# T-Board-45-85_PCB_-_v0_1.net
KiCad netlist of a schematic drawn in EAGLE
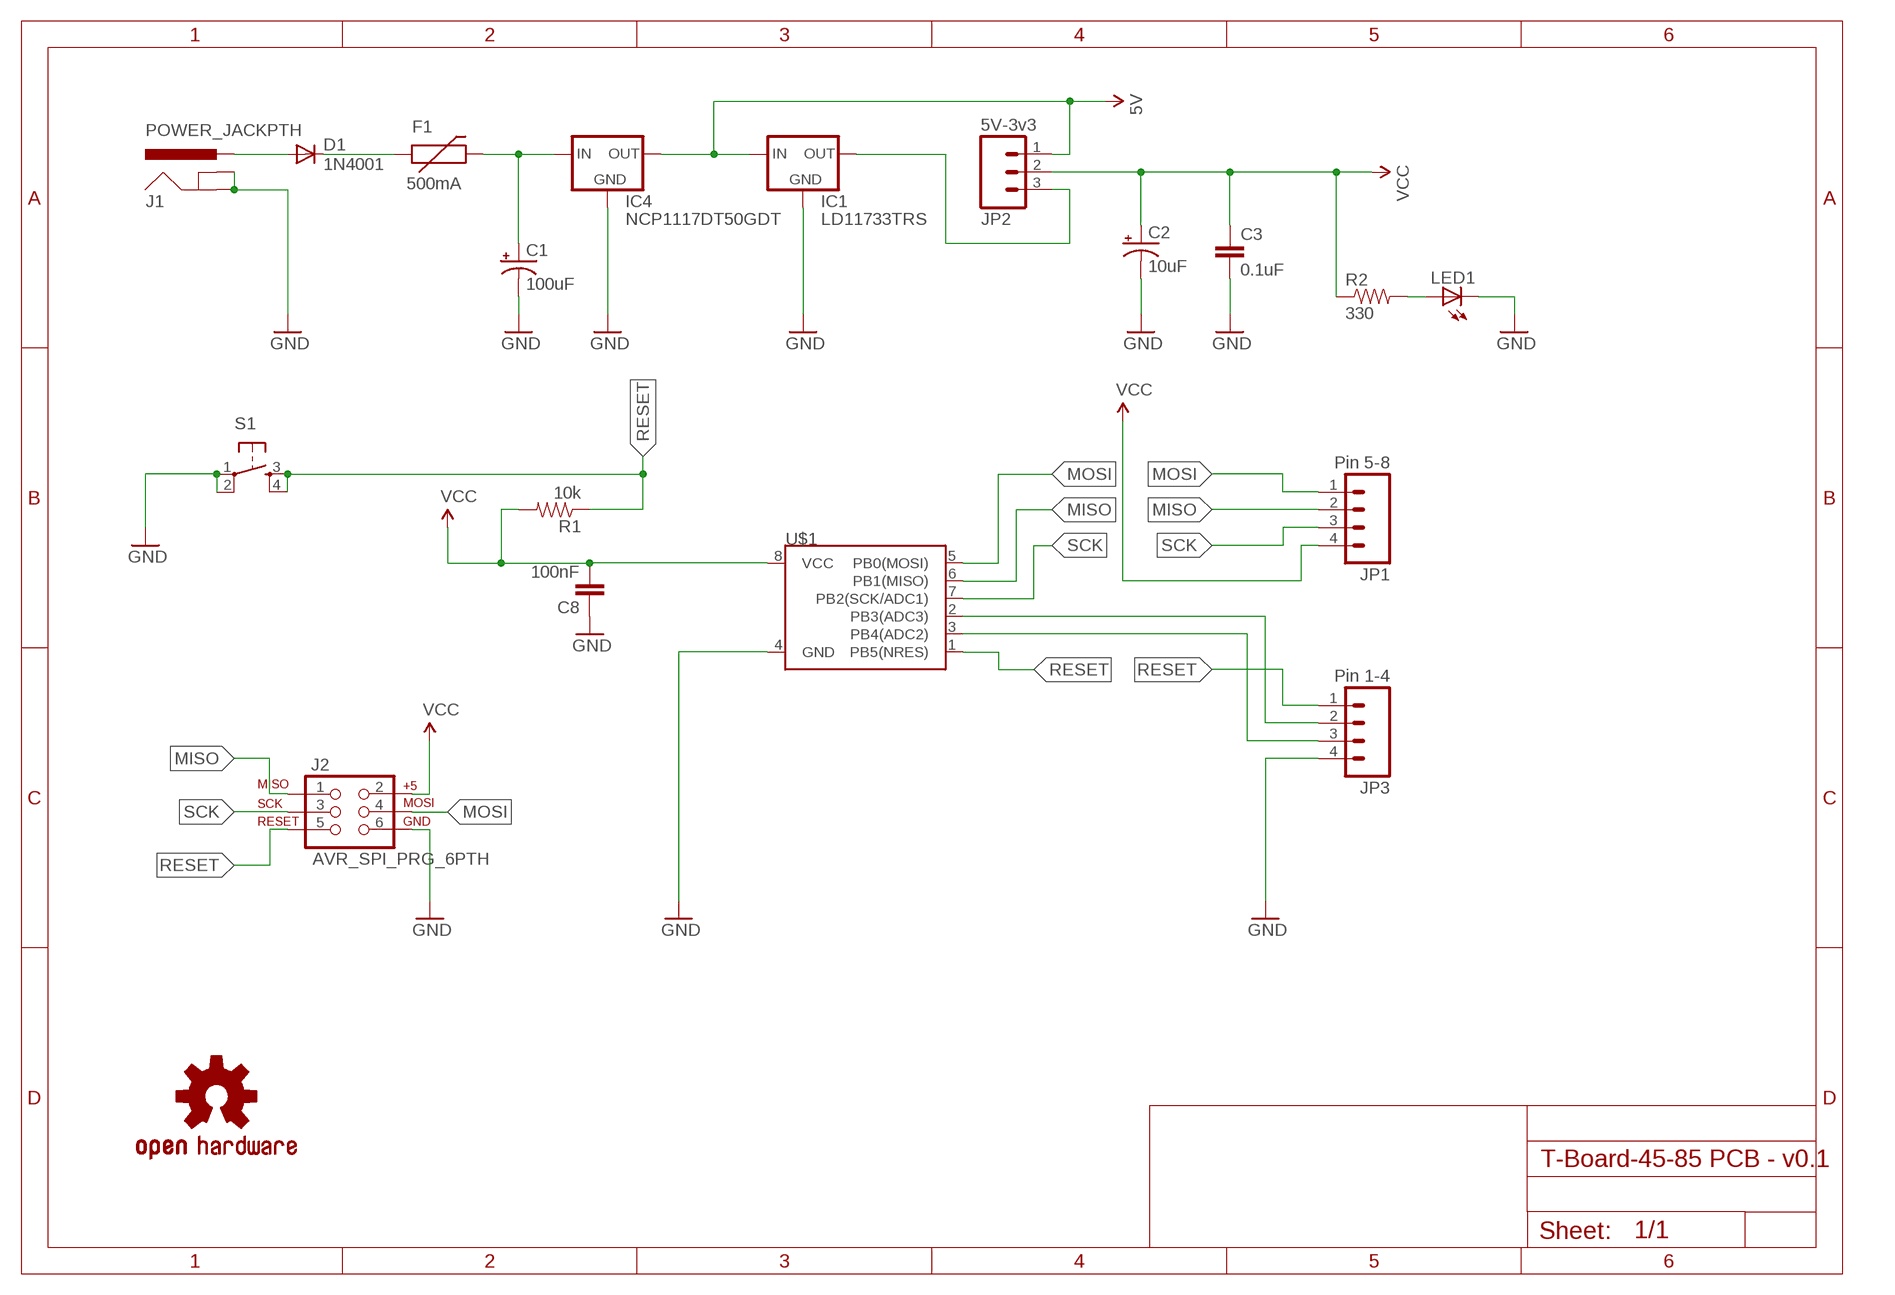
[diagram p0: schematic, sheet 1]

(export (version "E")
  (design (tool "Eeschema 10.0.6"))
  (components
    (comp (ref "C1")
      (value "100uF")
      (footprint "eagle-import:CPOL-RADIAL-100UF-25V")
      (libsource (lib "eagle-import") (part "CAP_POLPTH1"))
    )
    (comp (ref "C2")
      (value "10uF")
      (footprint "eagle-import:CPOL-RADIAL-10UF-25V")
      (libsource (lib "eagle-import") (part "CAP_POLPTH2"))
    )
    (comp (ref "C3")
      (value "0.1uF")
      (footprint "eagle-import:1206")
      (libsource (lib "eagle-import") (part "CAP1206"))
    )
    (comp (ref "C8")
      (value "100nF")
      (footprint "eagle-import:1206")
      (libsource (lib "eagle-import") (part "CAP1206"))
    )
    (comp (ref "D1")
      (value "1N4001")
      (footprint "eagle-import:DIODE-1N4001")
      (libsource (lib "eagle-import") (part "DIODEPTH"))
    )
    (comp (ref "F1")
      (value "500mA")
      (footprint "eagle-import:PTC")
      (libsource (lib "eagle-import") (part "PTCPTH"))
    )
    (comp (ref "IC1")
      (value "LD11733TRS")
      (footprint "eagle-import:SOT223")
      (libsource (lib "eagle-import") (part "LD117S33TR"))
    )
    (comp (ref "IC4")
      (value "NCP1117DT50GDT")
      (footprint "eagle-import:DPACK")
      (libsource (lib "eagle-import") (part "NCP1117DTDT50G"))
    )
    (comp (ref "J1")
      (value "POWER_JACKPTH")
      (footprint "eagle-import:POWER_JACK_PTH")
      (libsource (lib "eagle-import") (part "POWER_JACKPTH"))
    )
    (comp (ref "J2")
      (value "AVR_SPI_PRG_6PTH")
      (footprint "eagle-import:2X3")
      (libsource (lib "eagle-import") (part "AVR_SPI_PRG_6PTH"))
    )
    (comp (ref "JP1")
      (value "Pin 5-8")
      (footprint "eagle-import:1X04")
      (libsource (lib "eagle-import") (part "M04-NON-POLARPTH"))
    )
    (comp (ref "JP2")
      (value "5V-3v3")
      (footprint "eagle-import:1X03")
      (libsource (lib "eagle-import") (part "M03PTH"))
    )
    (comp (ref "JP3")
      (value "Pin 1-4")
      (footprint "eagle-import:1X04")
      (libsource (lib "eagle-import") (part "M04-NON-POLARPTH"))
    )
    (comp (ref "LED1")
      (value "LED1206")
      (footprint "eagle-import:LED-1206")
      (libsource (lib "eagle-import") (part "LED1206"))
    )
    (comp (ref "LOGO1")
      (value "OSHW-LOGOS")
      (footprint "eagle-import:OSHW-LOGO-S")
      (libsource (lib "eagle-import") (part "OSHW-LOGOS"))
    )
    (comp (ref "R1")
      (value "10k")
      (footprint "eagle-import:1206")
      (libsource (lib "eagle-import") (part "RESISTOR1206"))
    )
    (comp (ref "R2")
      (value "330")
      (footprint "eagle-import:1206")
      (libsource (lib "eagle-import") (part "RESISTOR1206"))
    )
    (comp (ref "S1")
      (value "TAC_SWITCHPTH")
      (footprint "eagle-import:TACTILE-PTH")
      (libsource (lib "eagle-import") (part "TAC_SWITCHPTH"))
    )
    (comp (ref "U$1")
      (value "ATTINY45TINY45-20-DIP")
      (footprint "eagle-import:DIP08")
      (libsource (lib "eagle-import") (part "ATTINY45TINY45-20-DIP"))
    )
  )
  (nets
    (net (code "1") (name "5V") (class "Default")
      (node (ref "IC1") (pin "3") (pinfunction "IN_3") (pintype "input"))
      (node (ref "IC4") (pin "4") (pinfunction "OUT_4") (pintype "passive"))
      (node (ref "JP2") (pin "1") (pinfunction "1_1") (pintype "passive"))
    )
    (net (code "2") (name "GND") (class "Default")
      (node (ref "C1") (pin "2") (pinfunction "-_2") (pintype "passive"))
      (node (ref "C2") (pin "2") (pinfunction "-_2") (pintype "passive"))
      (node (ref "C3") (pin "2") (pinfunction "2_2") (pintype "passive"))
      (node (ref "C8") (pin "1") (pinfunction "1_1") (pintype "passive"))
      (node (ref "IC1") (pin "1") (pinfunction "GND_1") (pintype "input"))
      (node (ref "IC4") (pin "1") (pinfunction "GND_1") (pintype "input"))
      (node (ref "J1") (pin "GND") (pinfunction "GND_GND") (pintype "bidirectional"))
      (node (ref "J1") (pin "GNDBREAK") (pinfunction "GNDBREAK_GNDBREAK") (pintype "bidirectional"))
      (node (ref "J2") (pin "6") (pinfunction "6_6") (pintype "passive"))
      (node (ref "JP3") (pin "4") (pinfunction "4_4") (pintype "passive"))
      (node (ref "LED1") (pin "C") (pinfunction "C_C") (pintype "passive"))
      (node (ref "S1") (pin "1") (pinfunction "1_1") (pintype "passive"))
      (node (ref "S1") (pin "2") (pinfunction "2_2") (pintype "passive"))
      (node (ref "U$1") (pin "4") (pinfunction "GND_4") (pintype "bidirectional"))
    )
    (net (code "3") (name "MISO") (class "Default")
      (node (ref "J2") (pin "1") (pinfunction "1_1") (pintype "passive"))
      (node (ref "JP1") (pin "2") (pinfunction "2_2") (pintype "passive"))
      (node (ref "U$1") (pin "6") (pinfunction "PB1(MISO)_6") (pintype "bidirectional"))
    )
    (net (code "4") (name "MOSI") (class "Default")
      (node (ref "J2") (pin "4") (pinfunction "4_4") (pintype "passive"))
      (node (ref "JP1") (pin "1") (pinfunction "1_1") (pintype "passive"))
      (node (ref "U$1") (pin "5") (pinfunction "PB0(MOSI)_5") (pintype "bidirectional"))
    )
    (net (code "5") (name "Net-(C1-+)") (class "Default")
      (node (ref "C1") (pin "1") (pinfunction "+_1") (pintype "passive"))
      (node (ref "F1") (pin "P$2") (pinfunction "2_P$2") (pintype "bidirectional"))
      (node (ref "IC4") (pin "3") (pinfunction "IN_3") (pintype "input"))
    )
    (net (code "6") (name "Net-(D1-PadA)") (class "Default")
      (node (ref "D1") (pin "A") (pinfunction "A_A") (pintype "passive"))
      (node (ref "J1") (pin "PWR") (pinfunction "PWR_PWR") (pintype "bidirectional"))
    )
    (net (code "7") (name "Net-(F1-1)") (class "Default")
      (node (ref "D1") (pin "C") (pinfunction "C_C") (pintype "passive"))
      (node (ref "F1") (pin "P$1") (pinfunction "1_P$1") (pintype "bidirectional"))
    )
    (net (code "8") (name "Net-(IC1-OUT)") (class "Default")
      (node (ref "IC1") (pin "4") (pinfunction "OUT_4") (pintype "passive"))
      (node (ref "JP2") (pin "3") (pinfunction "3_3") (pintype "passive"))
    )
    (net (code "9") (name "Net-(LED1-PadA)") (class "Default")
      (node (ref "LED1") (pin "A") (pinfunction "A_A") (pintype "passive"))
      (node (ref "R2") (pin "2") (pinfunction "2_2") (pintype "passive"))
    )
    (net (code "10") (name "Net-(U$1-PB3(ADC3))") (class "Default")
      (node (ref "JP3") (pin "2") (pinfunction "2_2") (pintype "passive"))
      (node (ref "U$1") (pin "2") (pinfunction "PB3(ADC3)_2") (pintype "bidirectional"))
    )
    (net (code "11") (name "Net-(U$1-PB4(ADC2))") (class "Default")
      (node (ref "JP3") (pin "3") (pinfunction "3_3") (pintype "passive"))
      (node (ref "U$1") (pin "3") (pinfunction "PB4(ADC2)_3") (pintype "bidirectional"))
    )
    (net (code "12") (name "RESET") (class "Default")
      (node (ref "J2") (pin "5") (pinfunction "5_5") (pintype "passive"))
      (node (ref "JP3") (pin "1") (pinfunction "1_1") (pintype "passive"))
      (node (ref "R1") (pin "1") (pinfunction "1_1") (pintype "passive"))
      (node (ref "S1") (pin "3") (pinfunction "3_3") (pintype "passive"))
      (node (ref "S1") (pin "4") (pinfunction "4_4") (pintype "passive"))
      (node (ref "U$1") (pin "1") (pinfunction "PB5(NRES)_1") (pintype "bidirectional"))
    )
    (net (code "13") (name "SCK") (class "Default")
      (node (ref "J2") (pin "3") (pinfunction "3_3") (pintype "passive"))
      (node (ref "JP1") (pin "3") (pinfunction "3_3") (pintype "passive"))
      (node (ref "U$1") (pin "7") (pinfunction "PB2(SCK/ADC1)_7") (pintype "bidirectional"))
    )
    (net (code "14") (name "VCC") (class "Default")
      (node (ref "C2") (pin "1") (pinfunction "+_1") (pintype "passive"))
      (node (ref "C3") (pin "1") (pinfunction "1_1") (pintype "passive"))
      (node (ref "C8") (pin "2") (pinfunction "2_2") (pintype "passive"))
      (node (ref "J2") (pin "2") (pinfunction "2_2") (pintype "passive"))
      (node (ref "JP1") (pin "4") (pinfunction "4_4") (pintype "passive"))
      (node (ref "JP2") (pin "2") (pinfunction "2_2") (pintype "passive"))
      (node (ref "R1") (pin "2") (pinfunction "2_2") (pintype "passive"))
      (node (ref "R2") (pin "1") (pinfunction "1_1") (pintype "passive"))
      (node (ref "U$1") (pin "8") (pinfunction "VCC_8") (pintype "bidirectional"))
    )
  )
)
